# QTPyNoisyBoi.net
KiCad netlist of a schematic drawn in EAGLE
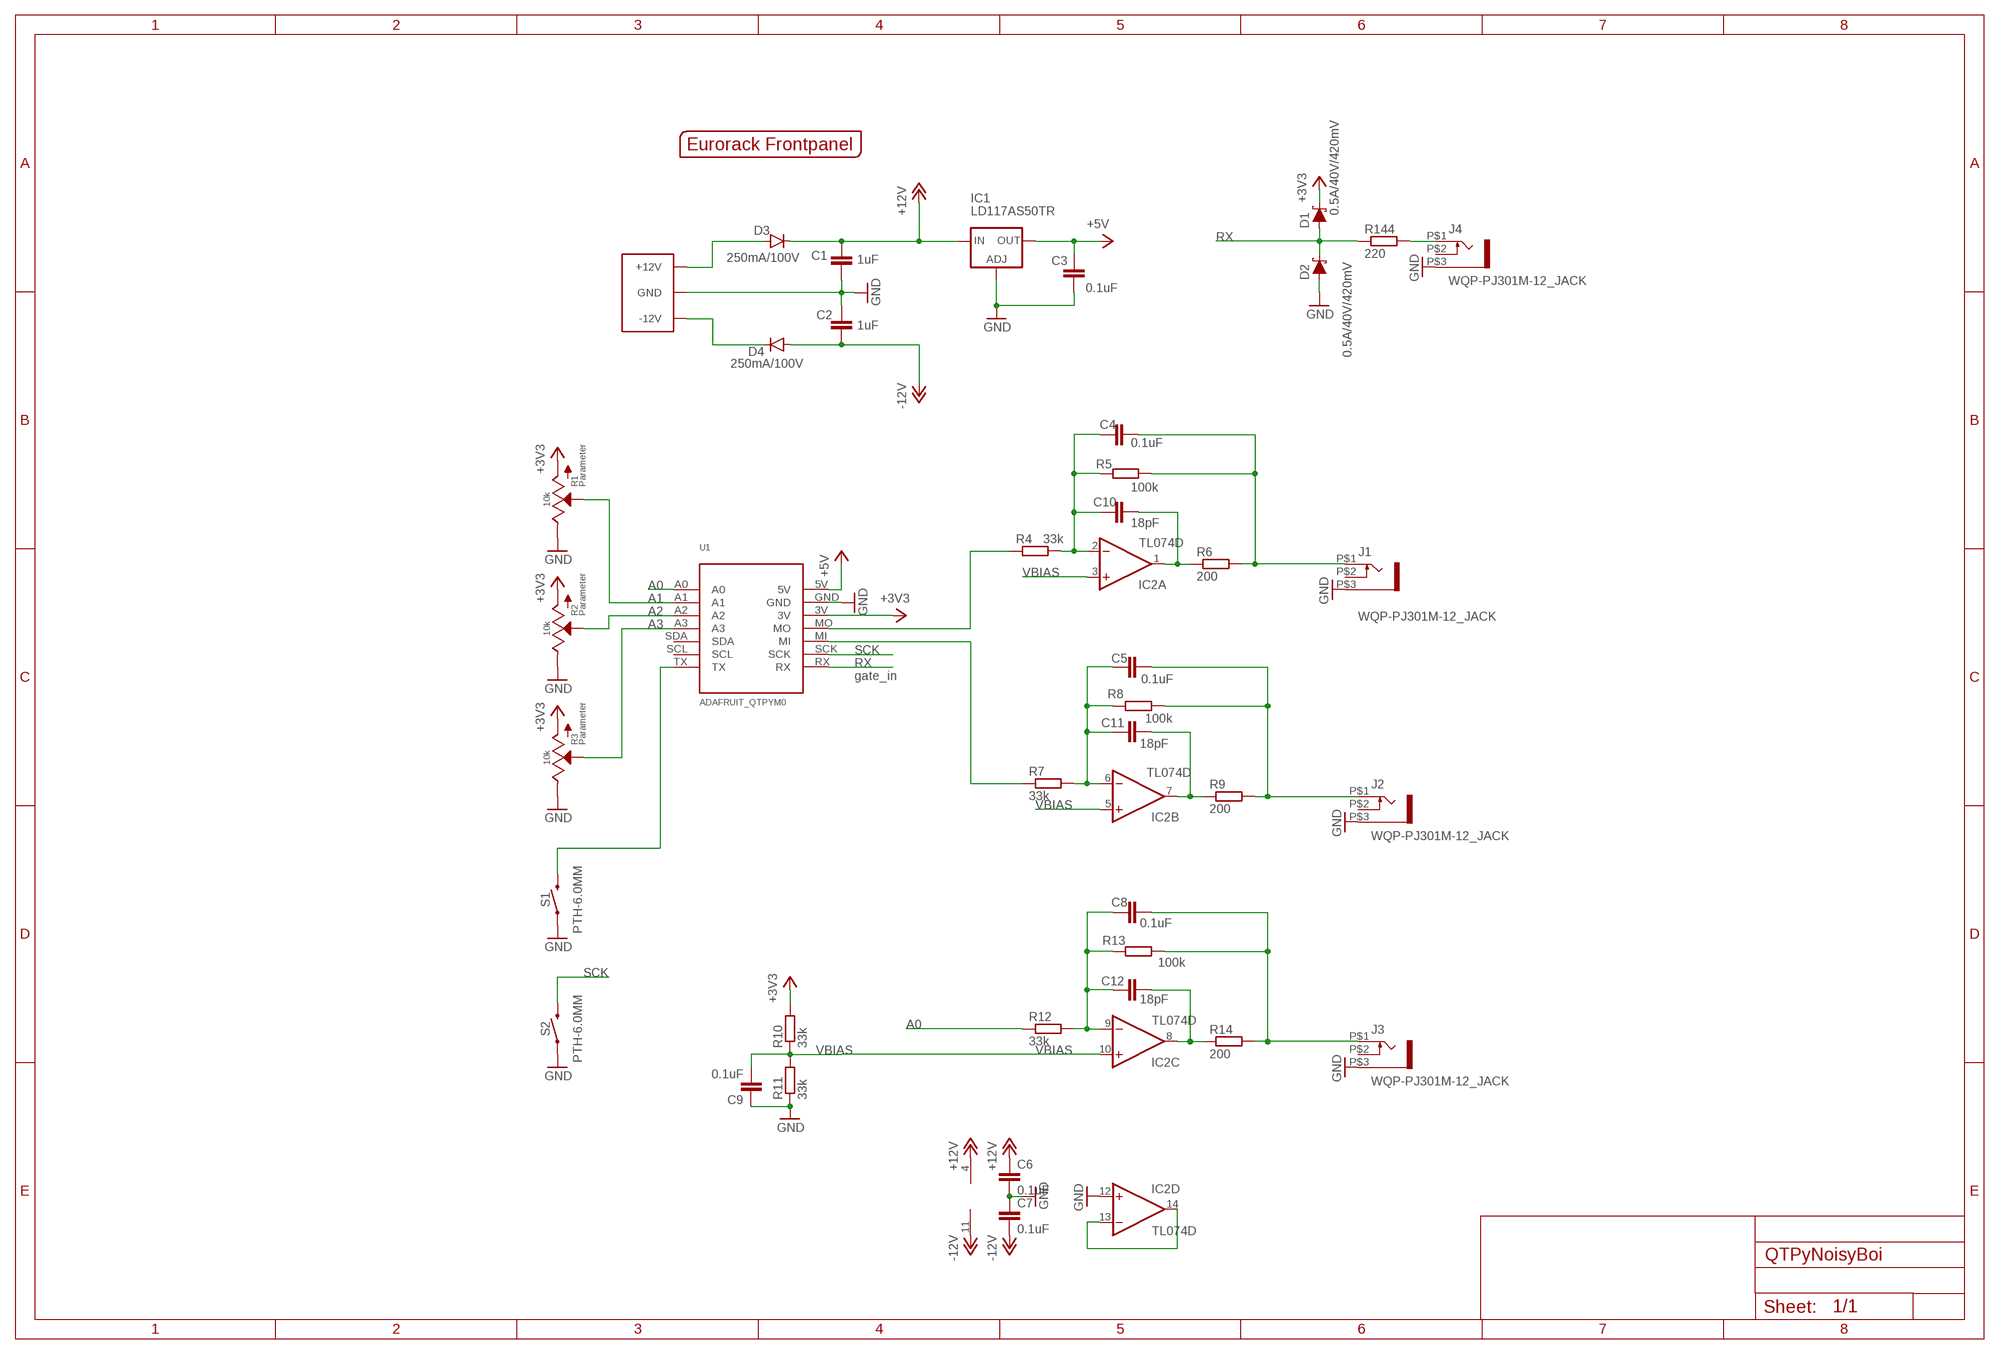
[diagram p0: schematic, sheet 1]

(export (version "E")
  (design (tool "Eeschema 10.0.6"))
  (components
    (comp (ref "C1")
      (value "1uF")
      (footprint "eagle-import:C0805")
      (libsource (lib "eagle-import") (part "C-EUC0805"))
    )
    (comp (ref "C2")
      (value "1uF")
      (footprint "eagle-import:C0805")
      (libsource (lib "eagle-import") (part "C-EUC0805"))
    )
    (comp (ref "C3")
      (value "0.1uF")
      (footprint "eagle-import:C0805")
      (libsource (lib "eagle-import") (part "C-EUC0805"))
    )
    (comp (ref "C4")
      (value "0.1uF")
      (footprint "eagle-import:C0805")
      (libsource (lib "eagle-import") (part "C-EUC0805"))
    )
    (comp (ref "C5")
      (value "0.1uF")
      (footprint "eagle-import:C0805")
      (libsource (lib "eagle-import") (part "C-EUC0805"))
    )
    (comp (ref "C6")
      (value "0.1uF")
      (footprint "eagle-import:C0805")
      (libsource (lib "eagle-import") (part "C-EUC0805"))
    )
    (comp (ref "C7")
      (value "0.1uF")
      (footprint "eagle-import:C0805")
      (libsource (lib "eagle-import") (part "C-EUC0805"))
    )
    (comp (ref "C8")
      (value "0.1uF")
      (footprint "eagle-import:C0805")
      (libsource (lib "eagle-import") (part "C-EUC0805"))
    )
    (comp (ref "C9")
      (value "0.1uF")
      (footprint "eagle-import:C0805")
      (libsource (lib "eagle-import") (part "C-EUC0805"))
    )
    (comp (ref "C10")
      (value "18pF")
      (footprint "eagle-import:C0805")
      (libsource (lib "eagle-import") (part "C-EUC0805"))
    )
    (comp (ref "C11")
      (value "18pF")
      (footprint "eagle-import:C0805")
      (libsource (lib "eagle-import") (part "C-EUC0805"))
    )
    (comp (ref "C12")
      (value "18pF")
      (footprint "eagle-import:C0805")
      (libsource (lib "eagle-import") (part "C-EUC0805"))
    )
    (comp (ref "D1")
      (value "0.5A/40V/420mV")
      (footprint "eagle-import:SOD-323")
      (libsource (lib "eagle-import") (part "DIODE-SCHOTTKY-PMEG4005EJ"))
    )
    (comp (ref "D2")
      (value "0.5A/40V/420mV")
      (footprint "eagle-import:SOD-323")
      (libsource (lib "eagle-import") (part "DIODE-SCHOTTKY-PMEG4005EJ"))
    )
    (comp (ref "D3")
      (value "250mA/100V")
      (footprint "eagle-import:SOD-323")
      (libsource (lib "eagle-import") (part "DIODEBAS16"))
    )
    (comp (ref "D4")
      (value "250mA/100V")
      (footprint "eagle-import:SOD-323")
      (libsource (lib "eagle-import") (part "DIODEBAS16"))
    )
    (comp (ref "DIM1")
      (value "EURO_POWER_LOCKSKINNY")
      (footprint "eagle-import:EURO_POWER_HEADER")
      (libsource (lib "eagle-import") (part "EURO_POWER_LOCKSKINNY"))
    )
    (comp (ref "IC1")
      (value "LD117AS50TR")
      (footprint "eagle-import:SOT223")
      (libsource (lib "eagle-import") (part "LD117A?S50TR"))
    )
    (comp (ref "IC2")
      (value "TL074D")
      (footprint "eagle-import:SO14")
      (libsource (lib "eagle-import") (part "TL074D"))
    )
    (comp (ref "J1")
      (value "WQP-PJ301M-12_JACK")
      (footprint "eagle-import:WQP-PJ301M-12_JACK")
      (libsource (lib "eagle-import") (part "WQP-PJ301M-12_JACK"))
    )
    (comp (ref "J2")
      (value "WQP-PJ301M-12_JACK")
      (footprint "eagle-import:WQP-PJ301M-12_JACK")
      (libsource (lib "eagle-import") (part "WQP-PJ301M-12_JACK"))
    )
    (comp (ref "J3")
      (value "WQP-PJ301M-12_JACK")
      (footprint "eagle-import:WQP-PJ301M-12_JACK")
      (libsource (lib "eagle-import") (part "WQP-PJ301M-12_JACK"))
    )
    (comp (ref "J4")
      (value "WQP-PJ301M-12_JACK")
      (footprint "eagle-import:WQP-PJ301M-12_JACK")
      (libsource (lib "eagle-import") (part "WQP-PJ301M-12_JACK"))
    )
    (comp (ref "R1")
      (value "10k")
      (footprint "eagle-import:OG-POTS_ALPS_POT_VERTICAL")
      (fields (field (name "DESC") "Parameter"))
      (libsource (lib "eagle-import") (part "POTZEPHPOT"))
    )
    (comp (ref "R2")
      (value "10k")
      (footprint "eagle-import:OG-POTS_ALPS_POT_VERTICAL")
      (fields (field (name "DESC") "Parameter"))
      (libsource (lib "eagle-import") (part "POTZEPHPOT"))
    )
    (comp (ref "R3")
      (value "10k")
      (footprint "eagle-import:OG-POTS_ALPS_POT_VERTICAL")
      (fields (field (name "DESC") "Parameter"))
      (libsource (lib "eagle-import") (part "POTZEPHPOT"))
    )
    (comp (ref "R4")
      (value "33k")
      (footprint "eagle-import:R0805")
      (libsource (lib "eagle-import") (part "R-EU_R0805"))
    )
    (comp (ref "R5")
      (value "100k")
      (footprint "eagle-import:R0805")
      (libsource (lib "eagle-import") (part "R-EU_R0805"))
    )
    (comp (ref "R6")
      (value "200")
      (footprint "eagle-import:R0805")
      (libsource (lib "eagle-import") (part "R-EU_R0805"))
    )
    (comp (ref "R7")
      (value "33k")
      (footprint "eagle-import:R0805")
      (libsource (lib "eagle-import") (part "R-EU_R0805"))
    )
    (comp (ref "R8")
      (value "100k")
      (footprint "eagle-import:R0805")
      (libsource (lib "eagle-import") (part "R-EU_R0805"))
    )
    (comp (ref "R9")
      (value "200")
      (footprint "eagle-import:R0805")
      (libsource (lib "eagle-import") (part "R-EU_R0805"))
    )
    (comp (ref "R10")
      (value "33k")
      (footprint "eagle-import:R0805")
      (libsource (lib "eagle-import") (part "R-EU_R0805"))
    )
    (comp (ref "R11")
      (value "33k")
      (footprint "eagle-import:R0805")
      (libsource (lib "eagle-import") (part "R-EU_R0805"))
    )
    (comp (ref "R12")
      (value "33k")
      (footprint "eagle-import:R0805")
      (libsource (lib "eagle-import") (part "R-EU_R0805"))
    )
    (comp (ref "R13")
      (value "100k")
      (footprint "eagle-import:R0805")
      (libsource (lib "eagle-import") (part "R-EU_R0805"))
    )
    (comp (ref "R14")
      (value "200")
      (footprint "eagle-import:R0805")
      (libsource (lib "eagle-import") (part "R-EU_R0805"))
    )
    (comp (ref "R144")
      (value "220")
      (footprint "eagle-import:R0805")
      (libsource (lib "eagle-import") (part "R-EU_R0805"))
    )
    (comp (ref "S1")
      (value "PTH-6.0MM")
      (footprint "eagle-import:TACTILE_SWITCH_PTH_6.0MM")
      (libsource (lib "eagle-import") (part "MOMENTARY-SWITCH-SPST-PTH-6.0MM"))
    )
    (comp (ref "S2")
      (value "PTH-6.0MM")
      (footprint "eagle-import:TACTILE_SWITCH_PTH_6.0MM")
      (libsource (lib "eagle-import") (part "MOMENTARY-SWITCH-SPST-PTH-6.0MM"))
    )
    (comp (ref "U$1")
      (value "EURORACK_PANEL6HP")
      (footprint "eagle-import:EURORACK6HPPANEL")
      (libsource (lib "eagle-import") (part "EURORACK_PANEL6HP"))
    )
    (comp (ref "U1")
      (value "ADAFRUIT_QTPYM0")
      (footprint "eagle-import:ADAFRUIT_QTPY_M0")
      (libsource (lib "eagle-import") (part "ADAFRUIT_QTPYM0"))
    )
  )
  (nets
    (net (code "1") (name "+3V3") (class "Default")
      (node (ref "D1") (pin "C") (pinfunction "C_C") (pintype "passive"))
      (node (ref "R1") (pin "P$3") (pinfunction "A_P$3") (pintype "passive"))
      (node (ref "R10") (pin "2") (pinfunction "2_2") (pintype "passive"))
      (node (ref "R2") (pin "P$3") (pinfunction "A_P$3") (pintype "passive"))
      (node (ref "R3") (pin "P$3") (pinfunction "A_P$3") (pintype "passive"))
      (node (ref "U1") (pin "3V") (pinfunction "3V_3V") (pintype "bidirectional"))
    )
    (net (code "2") (name "+5V") (class "Default")
      (node (ref "C3") (pin "2") (pinfunction "2_2") (pintype "passive"))
      (node (ref "IC1") (pin "4") (pinfunction "OUT_4") (pintype "passive"))
      (node (ref "U1") (pin "5V") (pinfunction "5V_5V") (pintype "bidirectional"))
    )
    (net (code "3") (name "+12V") (class "Default")
      (node (ref "C1") (pin "2") (pinfunction "2_2") (pintype "passive"))
      (node (ref "C6") (pin "1") (pinfunction "1_1") (pintype "passive"))
      (node (ref "D3") (pin "C") (pinfunction "C_C") (pintype "passive"))
      (node (ref "IC1") (pin "3") (pinfunction "IN_3") (pintype "input"))
      (node (ref "IC2") (pin "4") (pinfunction "V+_4") (pintype "power_in"))
    )
    (net (code "4") (name "-12V") (class "Default")
      (node (ref "C2") (pin "1") (pinfunction "1_1") (pintype "passive"))
      (node (ref "C7") (pin "2") (pinfunction "2_2") (pintype "passive"))
      (node (ref "D4") (pin "A") (pinfunction "A_A") (pintype "passive"))
      (node (ref "IC2") (pin "11") (pinfunction "V-_11") (pintype "power_in"))
    )
    (net (code "5") (name "/A0") (class "Default")
      (node (ref "R12") (pin "1") (pinfunction "1_1") (pintype "passive"))
      (node (ref "U1") (pin "A0") (pinfunction "A0_A0") (pintype "bidirectional"))
    )
    (net (code "6") (name "/A1") (class "Default")
      (node (ref "R1") (pin "P$2") (pinfunction "S_P$2") (pintype "passive"))
      (node (ref "U1") (pin "A1") (pinfunction "A1_A1") (pintype "bidirectional"))
    )
    (net (code "7") (name "/A2") (class "Default")
      (node (ref "R2") (pin "P$2") (pinfunction "S_P$2") (pintype "passive"))
      (node (ref "U1") (pin "A2") (pinfunction "A2_A2") (pintype "bidirectional"))
    )
    (net (code "8") (name "/A3") (class "Default")
      (node (ref "R3") (pin "P$2") (pinfunction "S_P$2") (pintype "passive"))
      (node (ref "U1") (pin "A3") (pinfunction "A3_A3") (pintype "bidirectional"))
    )
    (net (code "9") (name "/RX") (class "Default")
      (node (ref "D1") (pin "A") (pinfunction "A_A") (pintype "passive"))
      (node (ref "D2") (pin "C") (pinfunction "C_C") (pintype "passive"))
      (node (ref "R144") (pin "1") (pinfunction "1_1") (pintype "passive"))
      (node (ref "U1") (pin "RX") (pinfunction "RX_RX") (pintype "bidirectional"))
    )
    (net (code "10") (name "/SCK") (class "Default")
      (node (ref "S2") (pin "3") (pinfunction "2_3") (pintype "passive"))
      (node (ref "U1") (pin "SCK") (pinfunction "SCK_SCK") (pintype "bidirectional"))
    )
    (net (code "11") (name "/VBIAS") (class "Default")
      (node (ref "C9") (pin "2") (pinfunction "2_2") (pintype "passive"))
      (node (ref "IC2") (pin "10") (pinfunction "+IN_10") (pintype "input"))
      (node (ref "IC2") (pin "3") (pinfunction "+IN_3") (pintype "input"))
      (node (ref "IC2") (pin "5") (pinfunction "+IN_5") (pintype "input"))
      (node (ref "R10") (pin "1") (pinfunction "1_1") (pintype "passive"))
      (node (ref "R11") (pin "2") (pinfunction "2_2") (pintype "passive"))
    )
    (net (code "12") (name "GND") (class "Default")
      (node (ref "C1") (pin "1") (pinfunction "1_1") (pintype "passive"))
      (node (ref "C2") (pin "2") (pinfunction "2_2") (pintype "passive"))
      (node (ref "C3") (pin "1") (pinfunction "1_1") (pintype "passive"))
      (node (ref "C6") (pin "2") (pinfunction "2_2") (pintype "passive"))
      (node (ref "C7") (pin "1") (pinfunction "1_1") (pintype "passive"))
      (node (ref "C9") (pin "1") (pinfunction "1_1") (pintype "passive"))
      (node (ref "D2") (pin "A") (pinfunction "A_A") (pintype "passive"))
      (node (ref "DIM1") (pin "3") (pinfunction "GND_3") (pintype "bidirectional"))
      (node (ref "DIM1") (pin "4") (pinfunction "GND_4") (pintype "bidirectional"))
      (node (ref "DIM1") (pin "5") (pinfunction "GND_5") (pintype "bidirectional"))
      (node (ref "DIM1") (pin "6") (pinfunction "GND_6") (pintype "bidirectional"))
      (node (ref "DIM1") (pin "7") (pinfunction "GND_7") (pintype "bidirectional"))
      (node (ref "DIM1") (pin "8") (pinfunction "GND_8") (pintype "bidirectional"))
      (node (ref "IC1") (pin "1") (pinfunction "ADJ_1") (pintype "input"))
      (node (ref "IC2") (pin "12") (pinfunction "+IN_12") (pintype "input"))
      (node (ref "J1") (pin "P$3") (pinfunction "1_P$3") (pintype "passive"))
      (node (ref "J2") (pin "P$3") (pinfunction "1_P$3") (pintype "passive"))
      (node (ref "J3") (pin "P$3") (pinfunction "1_P$3") (pintype "passive"))
      (node (ref "J4") (pin "P$3") (pinfunction "1_P$3") (pintype "passive"))
      (node (ref "R1") (pin "P$1") (pinfunction "E_P$1") (pintype "passive"))
      (node (ref "R11") (pin "1") (pinfunction "1_1") (pintype "passive"))
      (node (ref "R2") (pin "P$1") (pinfunction "E_P$1") (pintype "passive"))
      (node (ref "R3") (pin "P$1") (pinfunction "E_P$1") (pintype "passive"))
      (node (ref "S1") (pin "1") (pinfunction "1_1") (pintype "passive"))
      (node (ref "S2") (pin "1") (pinfunction "1_1") (pintype "passive"))
      (node (ref "U1") (pin "GND") (pinfunction "GND_GND") (pintype "bidirectional"))
    )
    (net (code "13") (name "Net-(D3-PadA)") (class "Default")
      (node (ref "D3") (pin "A") (pinfunction "A_A") (pintype "passive"))
      (node (ref "DIM1") (pin "10") (pinfunction "+12V_10") (pintype "bidirectional"))
      (node (ref "DIM1") (pin "9") (pinfunction "+12V_9") (pintype "bidirectional"))
    )
    (net (code "14") (name "Net-(D4-PadC)") (class "Default")
      (node (ref "D4") (pin "C") (pinfunction "C_C") (pintype "passive"))
      (node (ref "DIM1") (pin "1") (pinfunction "-12V_1") (pintype "bidirectional"))
      (node (ref "DIM1") (pin "2") (pinfunction "-12V_2") (pintype "bidirectional"))
    )
    (net (code "15") (name "Net-(IC2A--IN)") (class "Default")
      (node (ref "C10") (pin "1") (pinfunction "1_1") (pintype "passive"))
      (node (ref "C4") (pin "1") (pinfunction "1_1") (pintype "passive"))
      (node (ref "IC2") (pin "2") (pinfunction "-IN_2") (pintype "input"))
      (node (ref "R4") (pin "2") (pinfunction "2_2") (pintype "passive"))
      (node (ref "R5") (pin "1") (pinfunction "1_1") (pintype "passive"))
    )
    (net (code "16") (name "Net-(IC2A-OUT)") (class "Default")
      (node (ref "C10") (pin "2") (pinfunction "2_2") (pintype "passive"))
      (node (ref "IC2") (pin "1") (pinfunction "OUT_1") (pintype "output"))
      (node (ref "R6") (pin "1") (pinfunction "1_1") (pintype "passive"))
    )
    (net (code "17") (name "Net-(IC2B--IN)") (class "Default")
      (node (ref "C11") (pin "1") (pinfunction "1_1") (pintype "passive"))
      (node (ref "C5") (pin "1") (pinfunction "1_1") (pintype "passive"))
      (node (ref "IC2") (pin "6") (pinfunction "-IN_6") (pintype "input"))
      (node (ref "R7") (pin "2") (pinfunction "2_2") (pintype "passive"))
      (node (ref "R8") (pin "1") (pinfunction "1_1") (pintype "passive"))
    )
    (net (code "18") (name "Net-(IC2B-OUT)") (class "Default")
      (node (ref "C11") (pin "2") (pinfunction "2_2") (pintype "passive"))
      (node (ref "IC2") (pin "7") (pinfunction "OUT_7") (pintype "output"))
      (node (ref "R9") (pin "1") (pinfunction "1_1") (pintype "passive"))
    )
    (net (code "19") (name "Net-(IC2C--IN)") (class "Default")
      (node (ref "C12") (pin "1") (pinfunction "1_1") (pintype "passive"))
      (node (ref "C8") (pin "1") (pinfunction "1_1") (pintype "passive"))
      (node (ref "IC2") (pin "9") (pinfunction "-IN_9") (pintype "input"))
      (node (ref "R12") (pin "2") (pinfunction "2_2") (pintype "passive"))
      (node (ref "R13") (pin "1") (pinfunction "1_1") (pintype "passive"))
    )
    (net (code "20") (name "Net-(IC2C-OUT)") (class "Default")
      (node (ref "C12") (pin "2") (pinfunction "2_2") (pintype "passive"))
      (node (ref "IC2") (pin "8") (pinfunction "OUT_8") (pintype "output"))
      (node (ref "R14") (pin "1") (pinfunction "1_1") (pintype "passive"))
    )
    (net (code "21") (name "Net-(IC2D--IN)") (class "Default")
      (node (ref "IC2") (pin "13") (pinfunction "-IN_13") (pintype "input"))
      (node (ref "IC2") (pin "14") (pinfunction "OUT_14") (pintype "output"))
    )
    (net (code "22") (name "Net-(J1-2)") (class "Default")
      (node (ref "C4") (pin "2") (pinfunction "2_2") (pintype "passive"))
      (node (ref "J1") (pin "P$1") (pinfunction "2_P$1") (pintype "passive"))
      (node (ref "R5") (pin "2") (pinfunction "2_2") (pintype "passive"))
      (node (ref "R6") (pin "2") (pinfunction "2_2") (pintype "passive"))
    )
    (net (code "23") (name "Net-(J2-2)") (class "Default")
      (node (ref "C5") (pin "2") (pinfunction "2_2") (pintype "passive"))
      (node (ref "J2") (pin "P$1") (pinfunction "2_P$1") (pintype "passive"))
      (node (ref "R8") (pin "2") (pinfunction "2_2") (pintype "passive"))
      (node (ref "R9") (pin "2") (pinfunction "2_2") (pintype "passive"))
    )
    (net (code "24") (name "Net-(J3-2)") (class "Default")
      (node (ref "C8") (pin "2") (pinfunction "2_2") (pintype "passive"))
      (node (ref "J3") (pin "P$1") (pinfunction "2_P$1") (pintype "passive"))
      (node (ref "R13") (pin "2") (pinfunction "2_2") (pintype "passive"))
      (node (ref "R14") (pin "2") (pinfunction "2_2") (pintype "passive"))
    )
    (net (code "25") (name "Net-(J4-2)") (class "Default")
      (node (ref "J4") (pin "P$1") (pinfunction "2_P$1") (pintype "passive"))
      (node (ref "R144") (pin "2") (pinfunction "2_2") (pintype "passive"))
    )
    (net (code "26") (name "Net-(R4-Pad1)") (class "Default")
      (node (ref "R4") (pin "1") (pinfunction "1_1") (pintype "passive"))
      (node (ref "U1") (pin "MO") (pinfunction "MO_MO") (pintype "bidirectional"))
    )
    (net (code "27") (name "Net-(R7-Pad1)") (class "Default")
      (node (ref "R7") (pin "1") (pinfunction "1_1") (pintype "passive"))
      (node (ref "U1") (pin "MI") (pinfunction "MI_MI") (pintype "bidirectional"))
    )
    (net (code "28") (name "Net-(S1-2)") (class "Default")
      (node (ref "S1") (pin "3") (pinfunction "2_3") (pintype "passive"))
      (node (ref "U1") (pin "TX") (pinfunction "TX_TX") (pintype "bidirectional"))
    )
    (net (code "29") (name "unconnected-(J1-3-PadP$2)") (class "Default")
      (node (ref "J1") (pin "P$2") (pinfunction "3_P$2") (pintype "passive"))
    )
    (net (code "30") (name "unconnected-(J2-3-PadP$2)") (class "Default")
      (node (ref "J2") (pin "P$2") (pinfunction "3_P$2") (pintype "passive"))
    )
    (net (code "31") (name "unconnected-(J3-3-PadP$2)") (class "Default")
      (node (ref "J3") (pin "P$2") (pinfunction "3_P$2") (pintype "passive"))
    )
    (net (code "32") (name "unconnected-(J4-3-PadP$2)") (class "Default")
      (node (ref "J4") (pin "P$2") (pinfunction "3_P$2") (pintype "passive"))
    )
    (net (code "33") (name "unconnected-(U1-PadSCL)") (class "Default")
      (node (ref "U1") (pin "SCL") (pinfunction "SCL_SCL") (pintype "bidirectional"))
    )
    (net (code "34") (name "unconnected-(U1-PadSDA)") (class "Default")
      (node (ref "U1") (pin "SDA") (pinfunction "SDA_SDA") (pintype "bidirectional"))
    )
  )
)
